# StartBase.net
KiCad netlist of a schematic drawn in EAGLE
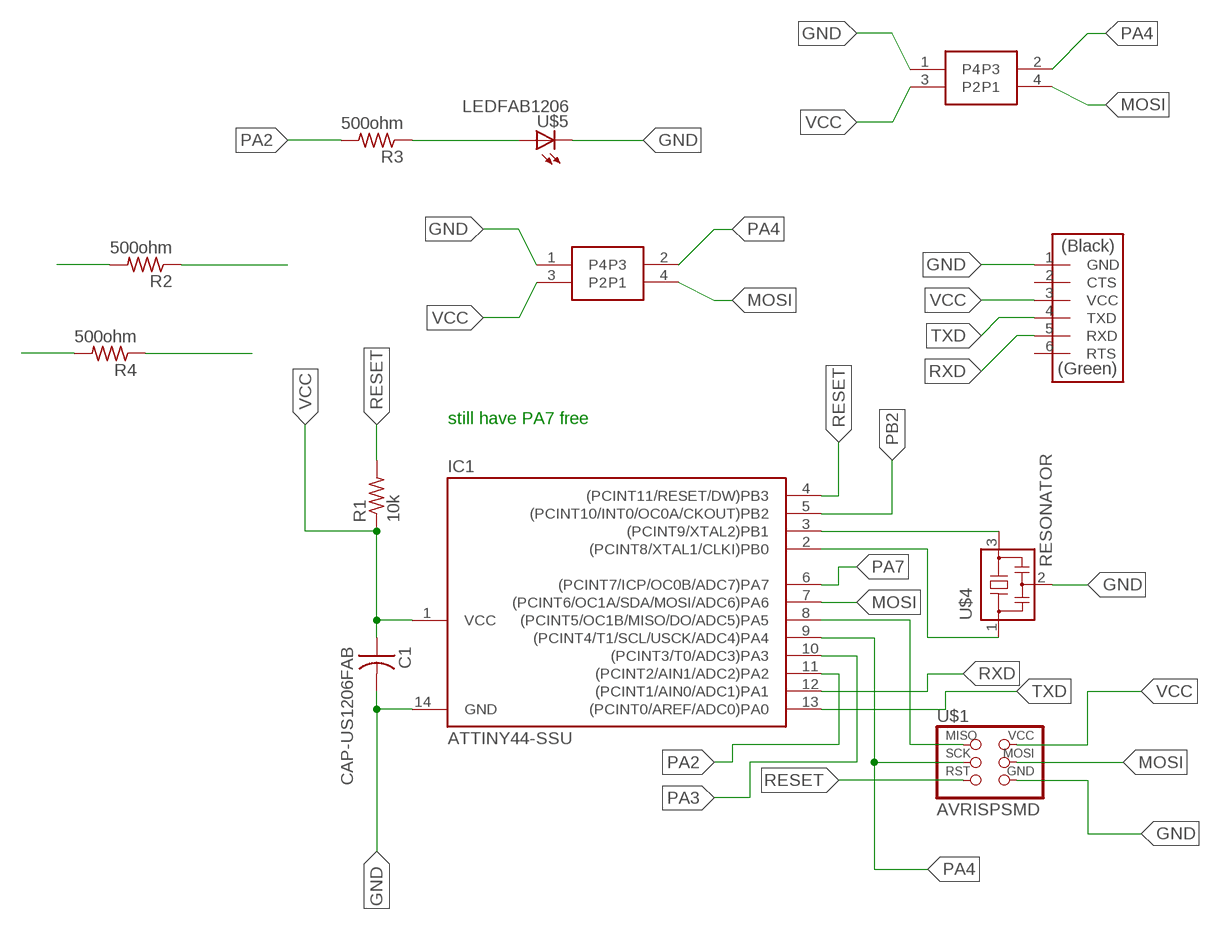
[diagram p0: schematic, sheet 1]

(export (version "E")
  (design (tool "Eeschema 10.0.6"))
  (components
    (comp (ref "C1")
      (value "CAP-US1206FAB")
      (footprint "eagle-import:C1206FAB")
      (libsource (lib "eagle-import") (part "CAP-US1206FAB"))
    )
    (comp (ref "IC1")
      (value "ATTINY44-SSU")
      (footprint "eagle-import:SOIC14")
      (libsource (lib "eagle-import") (part "ATTINY44-SSU"))
    )
    (comp (ref "R1")
      (value "10k")
      (footprint "eagle-import:R1206FAB")
      (libsource (lib "eagle-import") (part "RES-US1206FAB"))
    )
    (comp (ref "R2")
      (value "500ohm")
      (footprint "eagle-import:R1206FAB")
      (libsource (lib "eagle-import") (part "RES-US1206FAB"))
    )
    (comp (ref "R3")
      (value "500ohm")
      (footprint "eagle-import:R1206FAB")
      (libsource (lib "eagle-import") (part "RES-US1206FAB"))
    )
    (comp (ref "R4")
      (value "500ohm")
      (footprint "eagle-import:R1206FAB")
      (libsource (lib "eagle-import") (part "RES-US1206FAB"))
    )
    (comp (ref "U$1")
      (value "AVRISPSMD")
      (footprint "eagle-import:2X03SMD")
      (libsource (lib "eagle-import") (part "AVRISPSMD"))
    )
    (comp (ref "U$2")
      (value "FTDI-SMD-HEADER")
      (footprint "eagle-import:1X06SMD")
      (libsource (lib "eagle-import") (part "FTDI-SMD-HEADER"))
    )
    (comp (ref "U$3")
      (value "4PIN-SMD-CONNECTOR")
      (footprint "eagle-import:2X02SMD")
      (libsource (lib "eagle-import") (part "4PIN-SMD-CONNECTOR"))
    )
    (comp (ref "U$4")
      (value "RESONATOR")
      (footprint "eagle-import:EFOBM")
      (libsource (lib "eagle-import") (part "RESONATOR"))
    )
    (comp (ref "U$5")
      (value "LEDFAB1206")
      (footprint "eagle-import:LED1206FAB")
      (libsource (lib "eagle-import") (part "LEDFAB1206"))
    )
    (comp (ref "U$6")
      (value "4PIN-SMD-CONNECTOR")
      (footprint "eagle-import:2X02SMD")
      (libsource (lib "eagle-import") (part "4PIN-SMD-CONNECTOR"))
    )
  )
  (nets
    (net (code "1") (name "GND") (class "Default")
      (node (ref "C1") (pin "2") (pinfunction "2_2") (pintype "passive"))
      (node (ref "IC1") (pin "14") (pinfunction "GND_14") (pintype "power_in"))
      (node (ref "U$1") (pin "6") (pinfunction "GND_6") (pintype "passive"))
      (node (ref "U$2") (pin "1") (pinfunction "GND_1") (pintype "bidirectional"))
      (node (ref "U$3") (pin "1") (pinfunction "P4_1") (pintype "bidirectional"))
      (node (ref "U$4") (pin "2") (pinfunction "2_2") (pintype "passive"))
      (node (ref "U$5") (pin "2") (pinfunction "C_2") (pintype "passive"))
      (node (ref "U$6") (pin "1") (pinfunction "P4_1") (pintype "bidirectional"))
    )
    (net (code "2") (name "MOSI") (class "Default")
      (node (ref "IC1") (pin "7") (pinfunction "(PCINT6/OC1A/SDA/MOSI/ADC6)PA6_7") (pintype "bidirectional"))
      (node (ref "U$1") (pin "4") (pinfunction "MOSI_4") (pintype "passive"))
      (node (ref "U$3") (pin "4") (pinfunction "P1_4") (pintype "bidirectional"))
      (node (ref "U$6") (pin "4") (pinfunction "P1_4") (pintype "bidirectional"))
    )
    (net (code "3") (name "Net-(IC1-(PCINT5{slash}OC1B{slash}MISO{slash}DO{slash}ADC5)PA5)") (class "Default")
      (node (ref "IC1") (pin "8") (pinfunction "(PCINT5/OC1B/MISO/DO/ADC5)PA5_8") (pintype "bidirectional"))
      (node (ref "U$1") (pin "1") (pinfunction "MISO_1") (pintype "passive"))
    )
    (net (code "4") (name "Net-(IC1-(PCINT8{slash}XTAL1{slash}CLKI)PB0)") (class "Default")
      (node (ref "IC1") (pin "2") (pinfunction "(PCINT8/XTAL1/CLKI)PB0_2") (pintype "bidirectional"))
      (node (ref "U$4") (pin "1") (pinfunction "1_1") (pintype "passive"))
    )
    (net (code "5") (name "Net-(IC1-(PCINT9{slash}XTAL2)PB1)") (class "Default")
      (node (ref "IC1") (pin "3") (pinfunction "(PCINT9/XTAL2)PB1_3") (pintype "bidirectional"))
      (node (ref "U$4") (pin "3") (pinfunction "3_3") (pintype "passive"))
    )
    (net (code "6") (name "Net-(U$5-A)") (class "Default")
      (node (ref "R3") (pin "1") (pinfunction "1_1") (pintype "passive"))
      (node (ref "U$5") (pin "1") (pinfunction "A_1") (pintype "passive"))
    )
    (net (code "7") (name "PA2") (class "Default")
      (node (ref "IC1") (pin "11") (pinfunction "(PCINT2/AIN1/ADC2)PA2_11") (pintype "bidirectional"))
      (node (ref "R3") (pin "2") (pinfunction "2_2") (pintype "passive"))
    )
    (net (code "8") (name "PA3") (class "Default")
      (node (ref "IC1") (pin "10") (pinfunction "(PCINT3/T0/ADC3)PA3_10") (pintype "bidirectional"))
    )
    (net (code "9") (name "PA4") (class "Default")
      (node (ref "IC1") (pin "9") (pinfunction "(PCINT4/T1/SCL/USCK/ADC4)PA4_9") (pintype "bidirectional"))
      (node (ref "U$1") (pin "3") (pinfunction "SCK_3") (pintype "passive"))
      (node (ref "U$3") (pin "2") (pinfunction "P3_2") (pintype "bidirectional"))
      (node (ref "U$6") (pin "2") (pinfunction "P3_2") (pintype "bidirectional"))
    )
    (net (code "10") (name "PA7") (class "Default")
      (node (ref "IC1") (pin "6") (pinfunction "(PCINT7/ICP/OC0B/ADC7)PA7_6") (pintype "bidirectional"))
    )
    (net (code "11") (name "PB2") (class "Default")
      (node (ref "IC1") (pin "5") (pinfunction "(PCINT10/INT0/OC0A/CKOUT)PB2_5") (pintype "bidirectional"))
    )
    (net (code "12") (name "RESET") (class "Default")
      (node (ref "IC1") (pin "4") (pinfunction "(PCINT11/RESET/DW)PB3_4") (pintype "bidirectional"))
      (node (ref "R1") (pin "2") (pinfunction "2_2") (pintype "passive"))
      (node (ref "U$1") (pin "5") (pinfunction "RST_5") (pintype "passive"))
    )
    (net (code "13") (name "RXD") (class "Default")
      (node (ref "IC1") (pin "12") (pinfunction "(PCINT1/AIN0/ADC1)PA1_12") (pintype "bidirectional"))
      (node (ref "U$2") (pin "5") (pinfunction "RXD_5") (pintype "bidirectional"))
    )
    (net (code "14") (name "TXD") (class "Default")
      (node (ref "IC1") (pin "13") (pinfunction "(PCINT0/AREF/ADC0)PA0_13") (pintype "bidirectional"))
      (node (ref "U$2") (pin "4") (pinfunction "TXD_4") (pintype "bidirectional"))
    )
    (net (code "15") (name "VCC") (class "Default")
      (node (ref "C1") (pin "1") (pinfunction "1_1") (pintype "passive"))
      (node (ref "IC1") (pin "1") (pinfunction "VCC_1") (pintype "power_in"))
      (node (ref "R1") (pin "1") (pinfunction "1_1") (pintype "passive"))
      (node (ref "U$1") (pin "2") (pinfunction "VCC_2") (pintype "passive"))
      (node (ref "U$2") (pin "3") (pinfunction "VCC_3") (pintype "bidirectional"))
      (node (ref "U$3") (pin "3") (pinfunction "P2_3") (pintype "bidirectional"))
      (node (ref "U$6") (pin "3") (pinfunction "P2_3") (pintype "bidirectional"))
    )
    (net (code "16") (name "unconnected-(R2-Pad1)") (class "Default")
      (node (ref "R2") (pin "1") (pinfunction "1_1") (pintype "passive"))
    )
    (net (code "17") (name "unconnected-(R2-Pad2)") (class "Default")
      (node (ref "R2") (pin "2") (pinfunction "2_2") (pintype "passive"))
    )
    (net (code "18") (name "unconnected-(R4-Pad1)") (class "Default")
      (node (ref "R4") (pin "1") (pinfunction "1_1") (pintype "passive"))
    )
    (net (code "19") (name "unconnected-(R4-Pad2)") (class "Default")
      (node (ref "R4") (pin "2") (pinfunction "2_2") (pintype "passive"))
    )
    (net (code "20") (name "unconnected-(U$2-CTS-Pad2)") (class "Default")
      (node (ref "U$2") (pin "2") (pinfunction "CTS_2") (pintype "bidirectional"))
    )
    (net (code "21") (name "unconnected-(U$2-RTS-Pad6)") (class "Default")
      (node (ref "U$2") (pin "6") (pinfunction "RTS_6") (pintype "bidirectional"))
    )
  )
)
